# Screen.net
KiCad netlist of a schematic drawn in Altium Designer
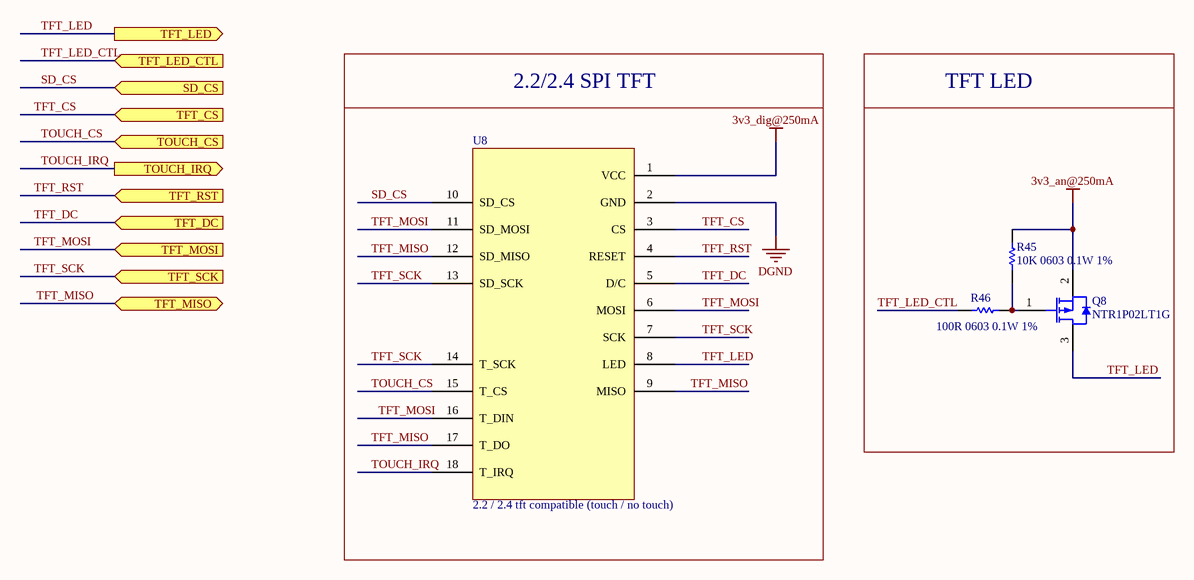
[diagram p0: Screen.SchDoc]

(export (version "E")
  (design (tool "Eeschema 10.0.6"))
  (components
    (comp (ref "Q8")
      (value "NTR1P02LT1G")
      (footprint "ONSC-SOT-23-3-318-08_V")
      (description "Power MOSFET, -20 V, -1.3 A, P-Channel, 3-Pin SOT-23, Pb-Free, Tape and Reel")
      (libsource (lib "CommunityVault") (part "ONSC-PMOS-G1S2D3-3_D"))
    )
    (comp (ref "R45")
      (value "10K 0603 0.1W 1%")
      (footprint "RESC1609X55X30ML10T20")
      (fields (field (name "TOLERANCE") "1%") (field (name "MANUFACTURER PART NUMBER") "ERJ-3GEYJ101V"))
      (libsource (lib "CommunityVault") (part "CMP-4716590-9"))
    )
    (comp (ref "R46")
      (value "100R 0603 0.1W 1%")
      (footprint "RESC1609X55X30ML10T20")
      (fields (field (name "MANUFACTURER PART NUMBER") "ERJ3GEYJ101V"))
      (libsource (lib "CommunityVault") (part "CMP-a61f6f36030f79d8-4"))
    )
    (comp (ref "U8")
      (value "2.2 / 2.4 tft compatible (touch / no touch)")
      (footprint "PCB-0iq7iyy8nrzrpmpo9lhg-1")
      (description "TZT 2.4\" 240x320 SPI TFT LCD Serial Port Module+5V/3.3V PBC Adapter Micro SD ILI9341")
      (libsource (lib "FavoritesLibrary") (part "SYM-m0xp0jkbbaqlzhag27re-1"))
    )
  )
  (nets
    (net (code "1") (name "/SD_CS") (class "Default")
      (node (ref "U8") (pin "10") (pinfunction "SD_CS_10") (pintype "passive"))
    )
    (net (code "2") (name "/TFT_CS") (class "Default")
      (node (ref "U8") (pin "3") (pinfunction "CS_3") (pintype "passive"))
    )
    (net (code "3") (name "/TFT_DC") (class "Default")
      (node (ref "U8") (pin "5") (pinfunction "D/C_5") (pintype "passive"))
    )
    (net (code "4") (name "/TFT_LED") (class "Default")
      (node (ref "Q8") (pin "3") (pinfunction "D_3") (pintype "passive"))
      (node (ref "U8") (pin "8") (pinfunction "LED_8") (pintype "passive"))
    )
    (net (code "5") (name "/TFT_LED_CTL") (class "Default")
      (node (ref "R46") (pin "2") (pinfunction "2_2") (pintype "passive"))
    )
    (net (code "6") (name "/TFT_MISO") (class "Default")
      (node (ref "U8") (pin "12") (pinfunction "SD_MISO_12") (pintype "passive"))
      (node (ref "U8") (pin "17") (pinfunction "T_DO_17") (pintype "passive"))
      (node (ref "U8") (pin "9") (pinfunction "MISO_9") (pintype "passive"))
    )
    (net (code "7") (name "/TFT_MOSI") (class "Default")
      (node (ref "U8") (pin "11") (pinfunction "SD_MOSI_11") (pintype "passive"))
      (node (ref "U8") (pin "16") (pinfunction "T_DIN_16") (pintype "passive"))
      (node (ref "U8") (pin "6") (pinfunction "MOSI_6") (pintype "passive"))
    )
    (net (code "8") (name "/TFT_RST") (class "Default")
      (node (ref "U8") (pin "4") (pinfunction "RESET_4") (pintype "passive"))
    )
    (net (code "9") (name "/TFT_SCK") (class "Default")
      (node (ref "U8") (pin "13") (pinfunction "SD_SCK_13") (pintype "passive"))
      (node (ref "U8") (pin "14") (pinfunction "T_SCK_14") (pintype "passive"))
      (node (ref "U8") (pin "7") (pinfunction "SCK_7") (pintype "passive"))
    )
    (net (code "10") (name "/TOUCH_CS") (class "Default")
      (node (ref "U8") (pin "15") (pinfunction "T_CS_15") (pintype "passive"))
    )
    (net (code "11") (name "/TOUCH_IRQ") (class "Default")
      (node (ref "U8") (pin "18") (pinfunction "T_IRQ_18") (pintype "passive"))
    )
    (net (code "12") (name "3v3_an@250mA") (class "Default")
      (node (ref "Q8") (pin "2") (pinfunction "S_2") (pintype "passive"))
      (node (ref "R45") (pin "1") (pinfunction "1_1") (pintype "passive"))
    )
    (net (code "13") (name "3v3_dig@250mA") (class "Default")
      (node (ref "U8") (pin "1") (pinfunction "VCC_1") (pintype "passive"))
    )
    (net (code "14") (name "DGND") (class "Default")
      (node (ref "U8") (pin "2") (pinfunction "GND_2") (pintype "passive"))
    )
    (net (code "15") (name "Net-(Q8-G)") (class "Default")
      (node (ref "Q8") (pin "1") (pinfunction "G_1") (pintype "passive"))
      (node (ref "R45") (pin "2") (pinfunction "2_2") (pintype "passive"))
      (node (ref "R46") (pin "1") (pinfunction "1_1") (pintype "passive"))
    )
  )
)
